# spi_barometer.net
KiCad netlist of a schematic drawn in EAGLE
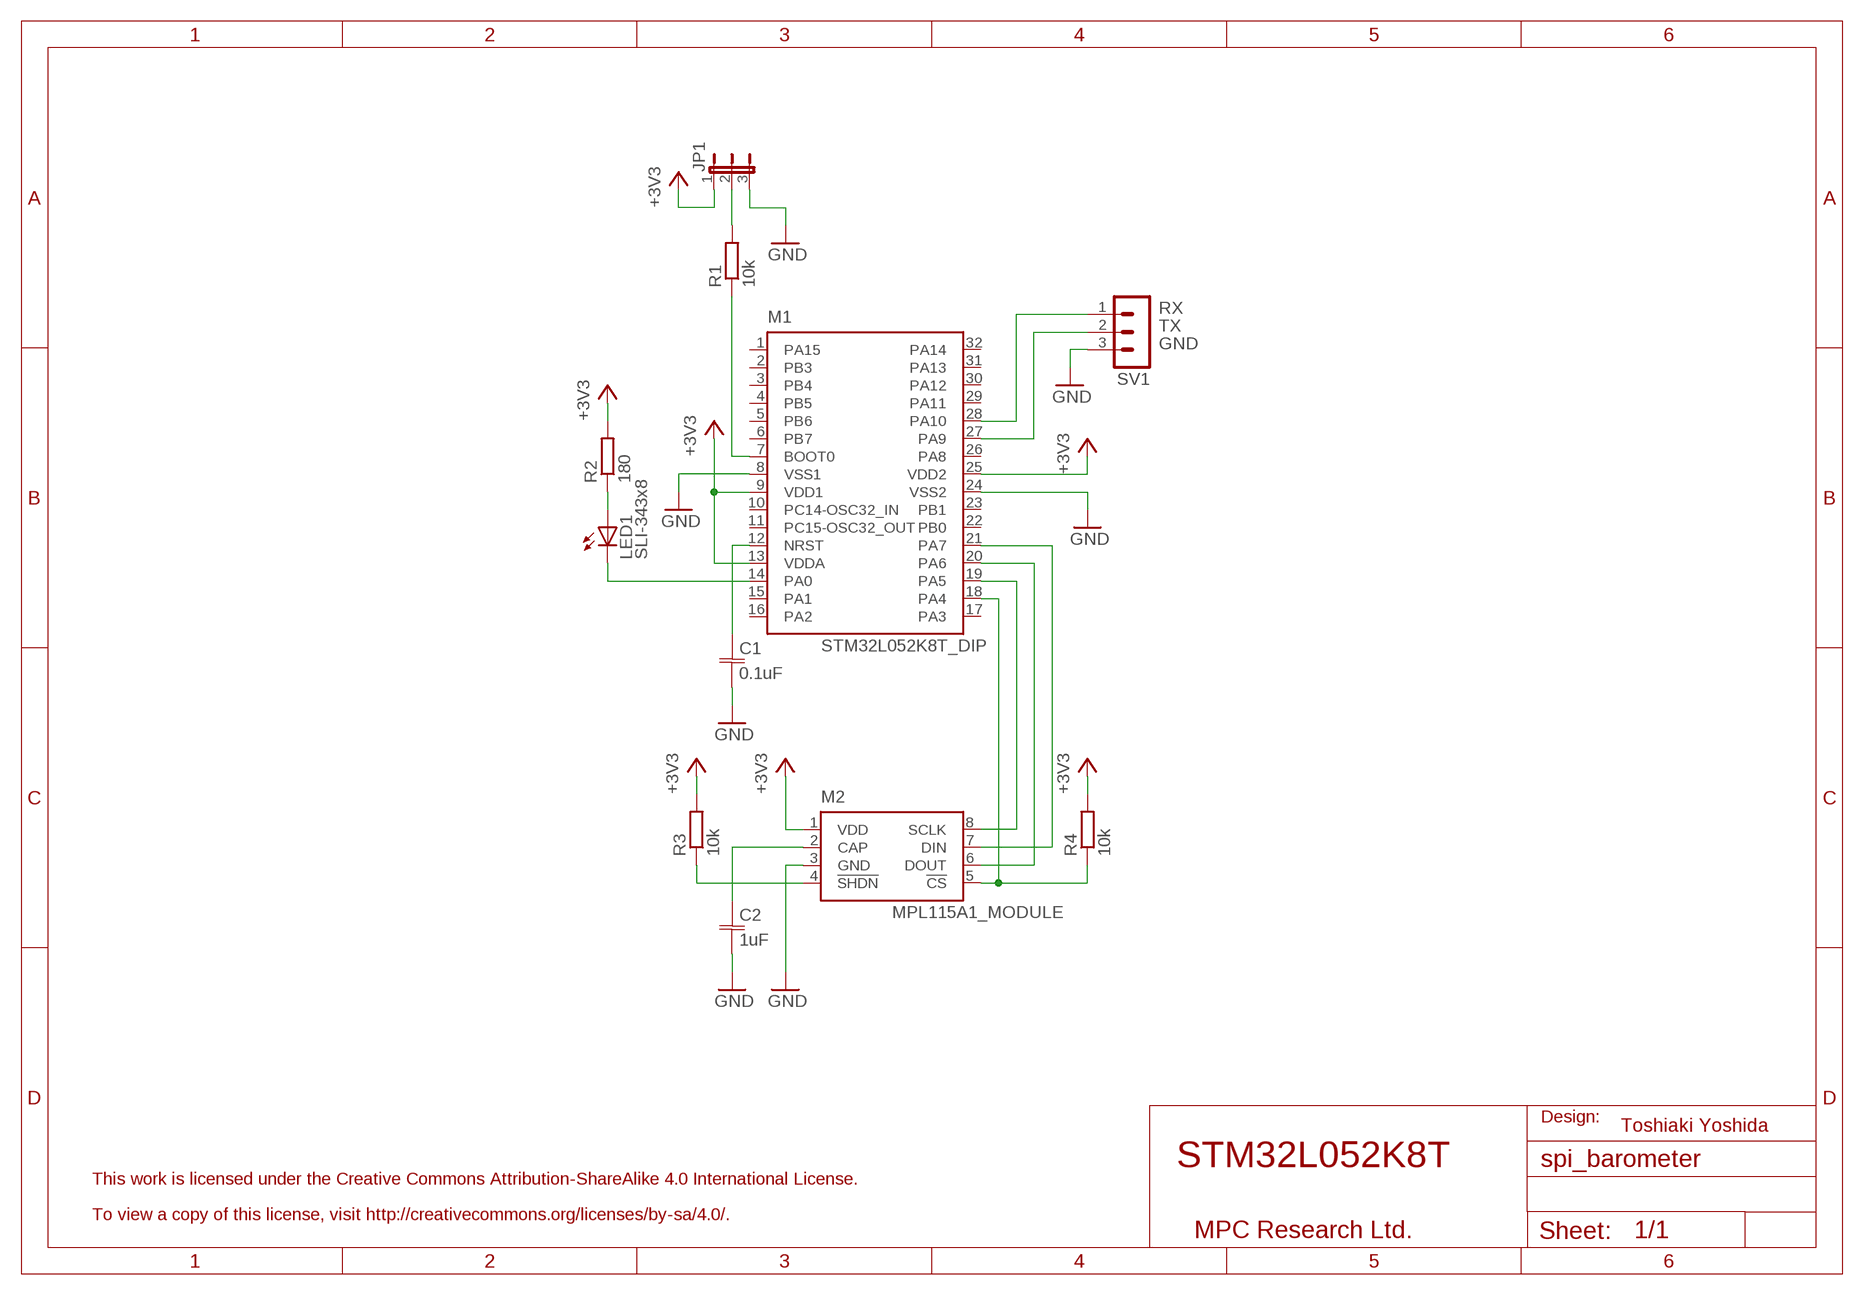
[diagram p0: schematic, sheet 1]

(export (version "E")
  (design (tool "Eeschema 10.0.6"))
  (components
    (comp (ref "C1")
      (value "0.1uF")
      (footprint "eagle-import:C050-024X044")
      (libsource (lib "eagle-import") (part "C-JIS050-024X044"))
    )
    (comp (ref "C2")
      (value "1uF")
      (footprint "eagle-import:C050-024X044")
      (libsource (lib "eagle-import") (part "C-JIS050-024X044"))
    )
    (comp (ref "JP1")
      (value "JP2E")
      (footprint "eagle-import:JP2")
      (libsource (lib "eagle-import") (part "JP2E"))
    )
    (comp (ref "LED1")
      (value "SLI-343x8")
      (footprint "eagle-import:LED3MM")
      (libsource (lib "eagle-import") (part "LED3MM"))
    )
    (comp (ref "M1")
      (value "STM32L052K8T_DIP")
      (footprint "eagle-import:DIP32")
      (libsource (lib "eagle-import") (part "STM32L052K8T_DIP"))
    )
    (comp (ref "M2")
      (value "MPL115A1_MODULE")
      (footprint "eagle-import:DIL8")
      (libsource (lib "eagle-import") (part "MPL115A1_MODULE"))
    )
    (comp (ref "R1")
      (value "10k")
      (footprint "eagle-import:0207_2V")
      (libsource (lib "eagle-import") (part "R-EU_0207/2V"))
    )
    (comp (ref "R2")
      (value "180")
      (footprint "eagle-import:0207_2V")
      (libsource (lib "eagle-import") (part "R-EU_0207/2V"))
    )
    (comp (ref "R3")
      (value "10k")
      (footprint "eagle-import:0207_2V")
      (libsource (lib "eagle-import") (part "R-EU_0207/2V"))
    )
    (comp (ref "R4")
      (value "10k")
      (footprint "eagle-import:0207_2V")
      (libsource (lib "eagle-import") (part "R-EU_0207/2V"))
    )
    (comp (ref "SV1")
      (value "MA03-1")
      (footprint "eagle-import:MA03-1")
      (libsource (lib "eagle-import") (part "MA03-1"))
    )
  )
  (nets
    (net (code "1") (name "+3V3") (class "Default")
      (node (ref "JP1") (pin "1") (pinfunction "1_1") (pintype "passive"))
      (node (ref "M1") (pin "13") (pinfunction "VDDA_13") (pintype "power_in"))
      (node (ref "M1") (pin "25") (pinfunction "VDD2_25") (pintype "bidirectional"))
      (node (ref "M1") (pin "9") (pinfunction "VDD1_9") (pintype "power_in"))
      (node (ref "M2") (pin "1") (pinfunction "VDD_1") (pintype "power_in"))
      (node (ref "R2") (pin "2") (pinfunction "2_2") (pintype "passive"))
      (node (ref "R3") (pin "2") (pinfunction "2_2") (pintype "passive"))
      (node (ref "R4") (pin "2") (pinfunction "2_2") (pintype "passive"))
    )
    (net (code "2") (name "GND") (class "Default")
      (node (ref "C1") (pin "2") (pinfunction "2_2") (pintype "passive"))
      (node (ref "C2") (pin "2") (pinfunction "2_2") (pintype "passive"))
      (node (ref "JP1") (pin "3") (pinfunction "3_3") (pintype "passive"))
      (node (ref "M1") (pin "24") (pinfunction "VSS2_24") (pintype "power_in"))
      (node (ref "M1") (pin "8") (pinfunction "VSS1_8") (pintype "power_in"))
      (node (ref "M2") (pin "3") (pinfunction "GND_3") (pintype "power_in"))
      (node (ref "SV1") (pin "3") (pinfunction "3_3") (pintype "passive"))
    )
    (net (code "3") (name "Net-(JP1-Pad2)") (class "Default")
      (node (ref "JP1") (pin "2") (pinfunction "2_2") (pintype "passive"))
      (node (ref "R1") (pin "2") (pinfunction "2_2") (pintype "passive"))
    )
    (net (code "4") (name "Net-(LED1-C)") (class "Default")
      (node (ref "LED1") (pin "K") (pinfunction "C_K") (pintype "passive"))
      (node (ref "M1") (pin "14") (pinfunction "PA0_14") (pintype "bidirectional"))
    )
    (net (code "5") (name "Net-(LED1-PadA)") (class "Default")
      (node (ref "LED1") (pin "A") (pinfunction "A_A") (pintype "passive"))
      (node (ref "R2") (pin "1") (pinfunction "1_1") (pintype "passive"))
    )
    (net (code "6") (name "Net-(M1-BOOT0)") (class "Default")
      (node (ref "M1") (pin "7") (pinfunction "BOOT0_7") (pintype "bidirectional"))
      (node (ref "R1") (pin "1") (pinfunction "1_1") (pintype "passive"))
    )
    (net (code "7") (name "Net-(M1-NRST)") (class "Default")
      (node (ref "C1") (pin "1") (pinfunction "1_1") (pintype "passive"))
      (node (ref "M1") (pin "12") (pinfunction "NRST_12") (pintype "bidirectional"))
    )
    (net (code "8") (name "Net-(M1-PA4)") (class "Default")
      (node (ref "M1") (pin "18") (pinfunction "PA4_18") (pintype "bidirectional"))
      (node (ref "M2") (pin "5") (pinfunction "~{CS}_5") (pintype "input"))
      (node (ref "R4") (pin "1") (pinfunction "1_1") (pintype "passive"))
    )
    (net (code "9") (name "Net-(M1-PA5)") (class "Default")
      (node (ref "M1") (pin "19") (pinfunction "PA5_19") (pintype "bidirectional"))
      (node (ref "M2") (pin "8") (pinfunction "SCLK_8") (pintype "input"))
    )
    (net (code "10") (name "Net-(M1-PA6)") (class "Default")
      (node (ref "M1") (pin "20") (pinfunction "PA6_20") (pintype "bidirectional"))
      (node (ref "M2") (pin "6") (pinfunction "DOUT_6") (pintype "output"))
    )
    (net (code "11") (name "Net-(M1-PA7)") (class "Default")
      (node (ref "M1") (pin "21") (pinfunction "PA7_21") (pintype "bidirectional"))
      (node (ref "M2") (pin "7") (pinfunction "DIN_7") (pintype "input"))
    )
    (net (code "12") (name "Net-(M1-PA9)") (class "Default")
      (node (ref "M1") (pin "27") (pinfunction "PA9_27") (pintype "bidirectional"))
      (node (ref "SV1") (pin "2") (pinfunction "2_2") (pintype "passive"))
    )
    (net (code "13") (name "Net-(M1-PA10)") (class "Default")
      (node (ref "M1") (pin "28") (pinfunction "PA10_28") (pintype "bidirectional"))
      (node (ref "SV1") (pin "1") (pinfunction "1_1") (pintype "passive"))
    )
    (net (code "14") (name "Net-(M2-CAP)") (class "Default")
      (node (ref "C2") (pin "1") (pinfunction "1_1") (pintype "passive"))
      (node (ref "M2") (pin "2") (pinfunction "CAP_2") (pintype "passive"))
    )
    (net (code "15") (name "Net-(M2-~{SHDN})") (class "Default")
      (node (ref "M2") (pin "4") (pinfunction "~{SHDN}_4") (pintype "input"))
      (node (ref "R3") (pin "1") (pinfunction "1_1") (pintype "passive"))
    )
    (net (code "16") (name "unconnected-(M1-PA1-Pad15)") (class "Default")
      (node (ref "M1") (pin "15") (pinfunction "PA1_15") (pintype "bidirectional"))
    )
    (net (code "17") (name "unconnected-(M1-PA2-Pad16)") (class "Default")
      (node (ref "M1") (pin "16") (pinfunction "PA2_16") (pintype "bidirectional"))
    )
    (net (code "18") (name "unconnected-(M1-PA3-Pad17)") (class "Default")
      (node (ref "M1") (pin "17") (pinfunction "PA3_17") (pintype "bidirectional"))
    )
    (net (code "19") (name "unconnected-(M1-PA8-Pad26)") (class "Default")
      (node (ref "M1") (pin "26") (pinfunction "PA8_26") (pintype "bidirectional"))
    )
    (net (code "20") (name "unconnected-(M1-PA11-Pad29)") (class "Default")
      (node (ref "M1") (pin "29") (pinfunction "PA11_29") (pintype "bidirectional"))
    )
    (net (code "21") (name "unconnected-(M1-PA12-Pad30)") (class "Default")
      (node (ref "M1") (pin "30") (pinfunction "PA12_30") (pintype "bidirectional"))
    )
    (net (code "22") (name "unconnected-(M1-PA13-Pad31)") (class "Default")
      (node (ref "M1") (pin "31") (pinfunction "PA13_31") (pintype "bidirectional"))
    )
    (net (code "23") (name "unconnected-(M1-PA14-Pad32)") (class "Default")
      (node (ref "M1") (pin "32") (pinfunction "PA14_32") (pintype "bidirectional"))
    )
    (net (code "24") (name "unconnected-(M1-PA15-Pad1)") (class "Default")
      (node (ref "M1") (pin "1") (pinfunction "PA15_1") (pintype "bidirectional"))
    )
    (net (code "25") (name "unconnected-(M1-PB0-Pad22)") (class "Default")
      (node (ref "M1") (pin "22") (pinfunction "PB0_22") (pintype "bidirectional"))
    )
    (net (code "26") (name "unconnected-(M1-PB1-Pad23)") (class "Default")
      (node (ref "M1") (pin "23") (pinfunction "PB1_23") (pintype "bidirectional"))
    )
    (net (code "27") (name "unconnected-(M1-PB3-Pad2)") (class "Default")
      (node (ref "M1") (pin "2") (pinfunction "PB3_2") (pintype "bidirectional"))
    )
    (net (code "28") (name "unconnected-(M1-PB4-Pad3)") (class "Default")
      (node (ref "M1") (pin "3") (pinfunction "PB4_3") (pintype "bidirectional"))
    )
    (net (code "29") (name "unconnected-(M1-PB5-Pad4)") (class "Default")
      (node (ref "M1") (pin "4") (pinfunction "PB5_4") (pintype "bidirectional"))
    )
    (net (code "30") (name "unconnected-(M1-PB6-Pad5)") (class "Default")
      (node (ref "M1") (pin "5") (pinfunction "PB6_5") (pintype "bidirectional"))
    )
    (net (code "31") (name "unconnected-(M1-PB7-Pad6)") (class "Default")
      (node (ref "M1") (pin "6") (pinfunction "PB7_6") (pintype "bidirectional"))
    )
    (net (code "32") (name "unconnected-(M1-PC14-OSC32_IN-Pad10)") (class "Default")
      (node (ref "M1") (pin "10") (pinfunction "PC14-OSC32_IN_10") (pintype "bidirectional"))
    )
    (net (code "33") (name "unconnected-(M1-PC15-OSC32_OUT-Pad11)") (class "Default")
      (node (ref "M1") (pin "11") (pinfunction "PC15-OSC32_OUT_11") (pintype "bidirectional"))
    )
  )
)
